# PIN_bias_voltage.net
KiCad netlist of a schematic drawn in Altium Designer
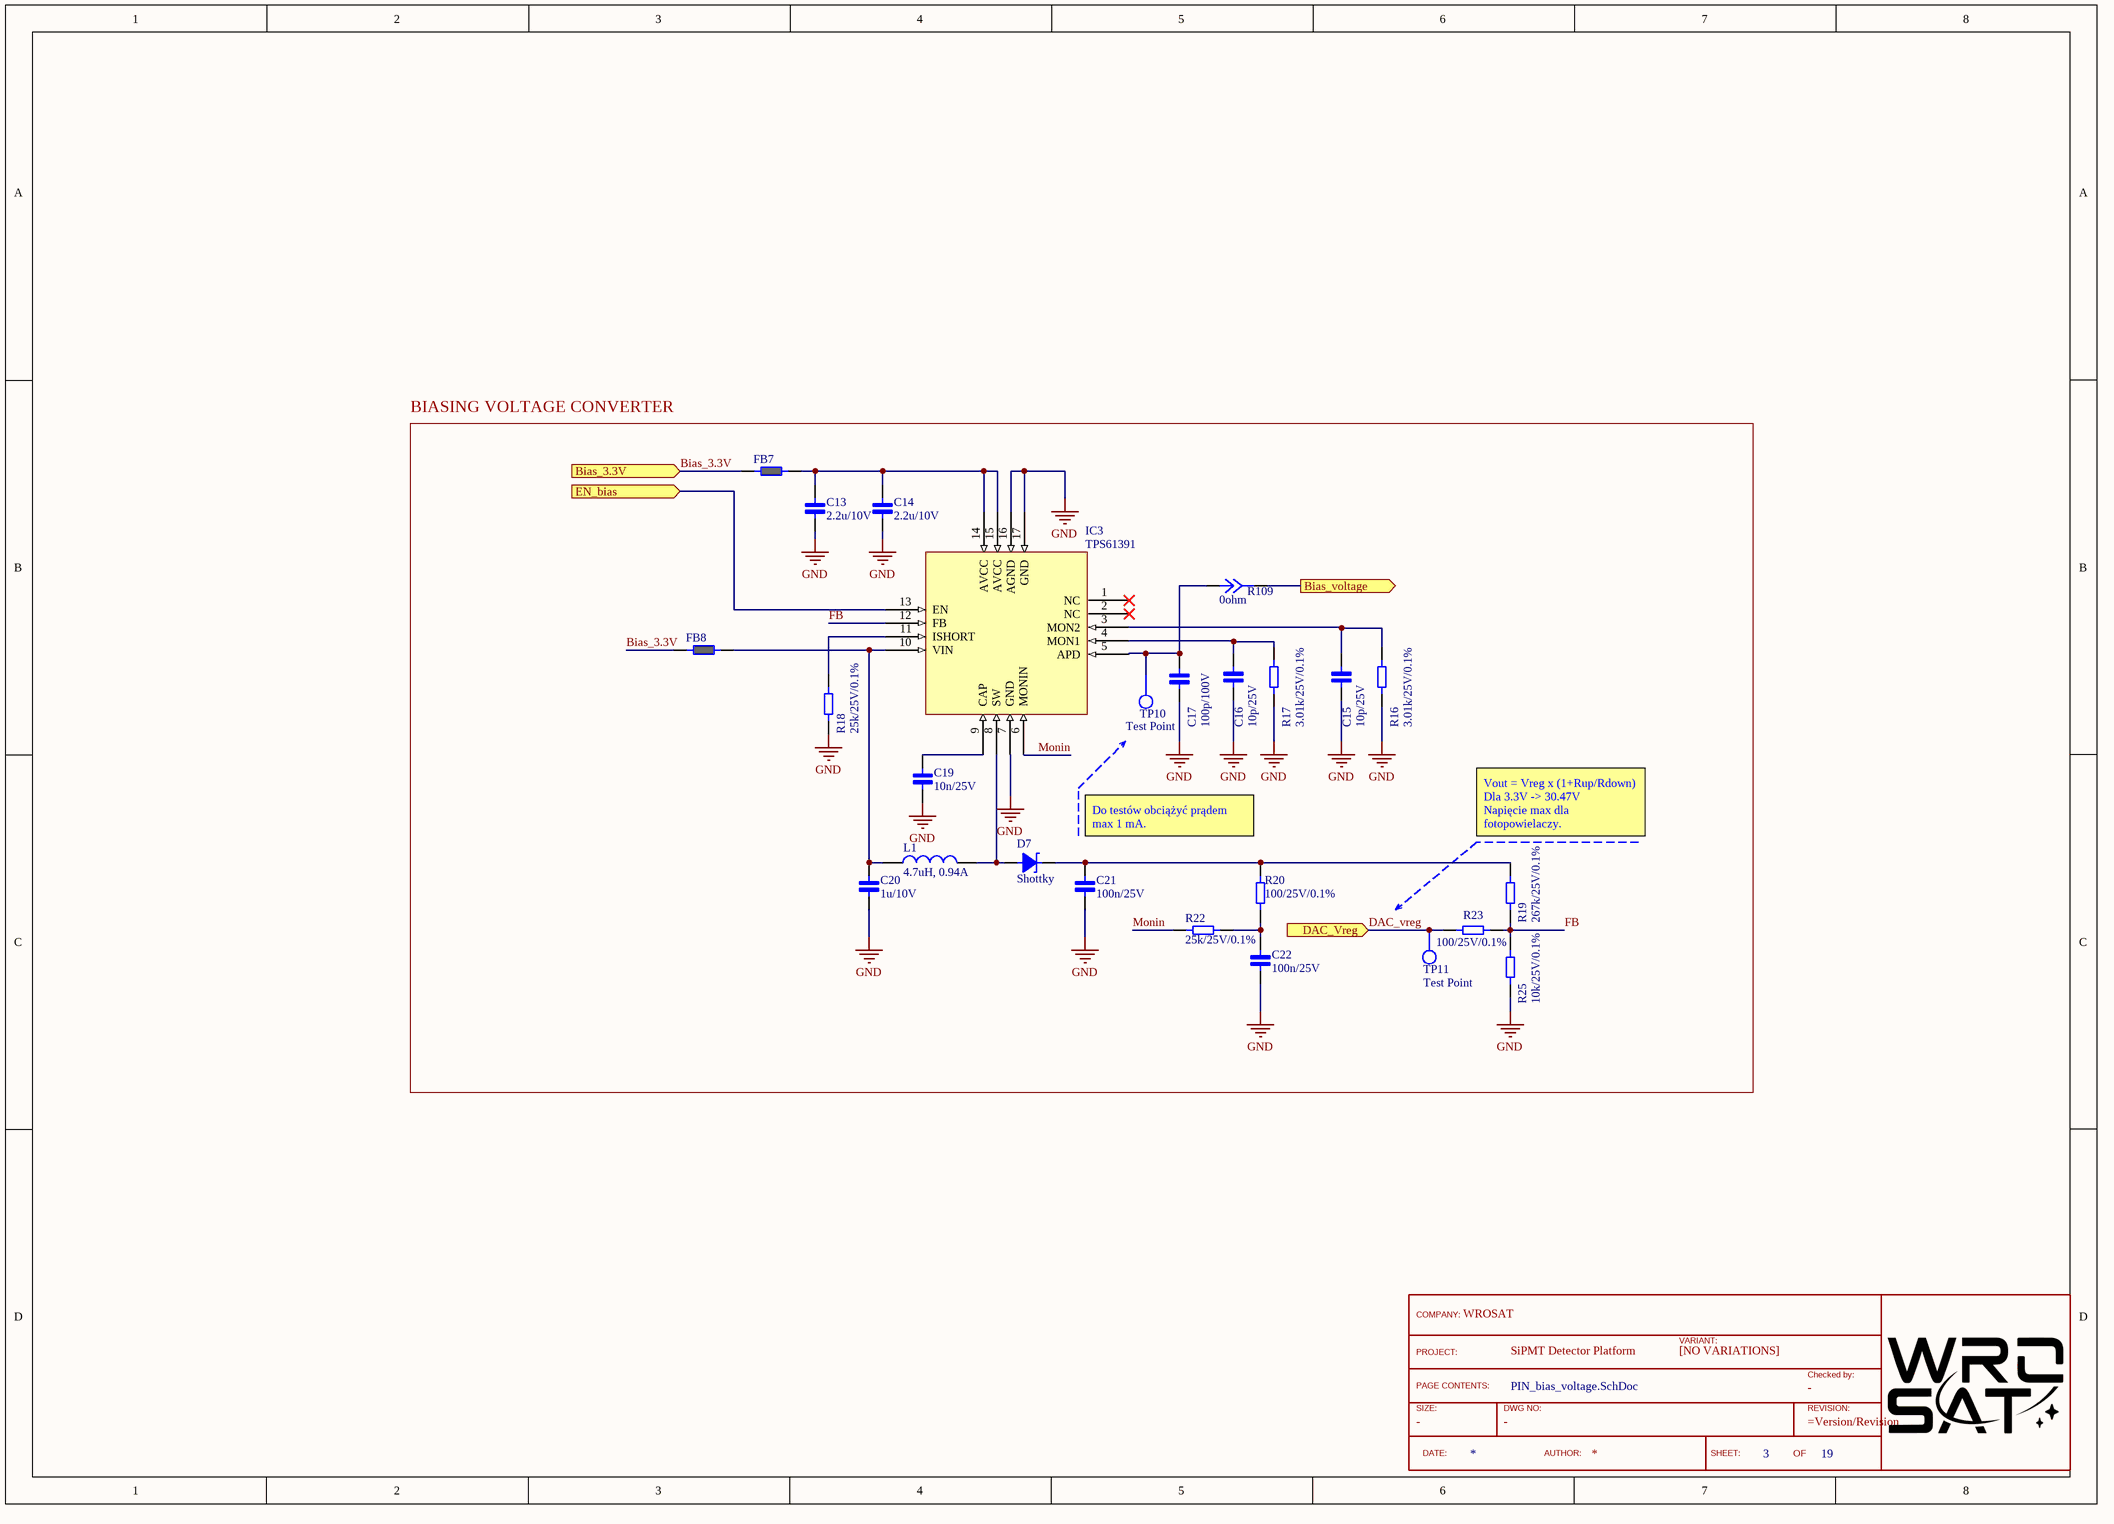
[diagram p0: PIN_bias_voltage.SchDoc]

(export (version "E")
  (design (tool "Eeschema 10.0.6"))
  (components
    (comp (ref "C13")
      (value "2.2u/10V")
      (footprint "Cap_0402")
      (description "Ceramic Capacitor 2.2uF / 0402 / 10V / ±5%, Wurth Elektronik MLCC")
      (libsource (lib "Cubesat_lib") (part "Cap_0402_2.2u"))
    )
    (comp (ref "C14")
      (value "2.2u/10V")
      (footprint "Cap_0402")
      (description "Ceramic Capacitor 2.2uF / 0402 / 10V / ±5%, Wurth Elektronik MLCC")
      (libsource (lib "Cubesat_lib") (part "Cap_0402_2.2u"))
    )
    (comp (ref "C15")
      (value "10p/25V")
      (footprint "Cap_0402")
      (description "0402 / 25V / ±5%, Wurth Elektronik MLCC")
      (libsource (lib "Cubesat_lib") (part "Cap_0402_10p"))
    )
    (comp (ref "C16")
      (value "10p/25V")
      (footprint "Cap_0402")
      (description "0402 / 25V / ±5%, Wurth Elektronik MLCC")
      (libsource (lib "Cubesat_lib") (part "Cap_0402_10p"))
    )
    (comp (ref "C17")
      (value "100p/100V")
      (footprint "Cap_0402")
      (description "0402 / 100V / ±5%, Wurth Elektronik MLCC")
      (libsource (lib "Cubesat_lib") (part "Cap_0402_100p_hv"))
    )
    (comp (ref "C19")
      (value "10n/25V")
      (footprint "Cap_0402")
      (description "Ceramic Capacitor 10n / 0402 / 25V / ±5%, Wurth Elektronik MLCC")
      (libsource (lib "Cubesat_lib") (part "Cap_0402_10n"))
    )
    (comp (ref "C20")
      (value "1u/10V")
      (footprint "Cap_0402")
      (description "Ceramic Capacitor 1uF / 0402 / 10V / ±5%, Wurth Elektronik MLCC")
      (libsource (lib "Cubesat_lib") (part "Cap_0402_1u"))
    )
    (comp (ref "C21")
      (value "100n/25V")
      (footprint "Cap_0402")
      (description "Ceramic Capacitor 100n / 0402 / 25V / ±5%, Wurth Elektronik MLCC")
      (libsource (lib "Cubesat_lib") (part "Cap_0402_100n"))
    )
    (comp (ref "C22")
      (value "100n/25V")
      (footprint "Cap_0402")
      (description "Ceramic Capacitor 100n / 0402 / 25V / ±5%, Wurth Elektronik MLCC")
      (libsource (lib "Cubesat_lib") (part "Cap_0402_100n"))
    )
    (comp (ref "D7")
      (value "Shottky")
      (footprint "SOD323")
      (description "Schottky diode, 90V, 100mA, 1.2V, 4ns")
      (libsource (lib "Cubesat_lib") (part "1SS355VMFHTE-17"))
    )
    (comp (ref "FB7")
      (value "Ferrite_bead_0402")
      (footprint "FERRITE_0402")
      (description "Ferrite bead, wurth 74269241102")
      (libsource (lib "Cubesat_lib") (part "Ferrite_bead_0402"))
    )
    (comp (ref "FB8")
      (value "Ferrite_bead_0402")
      (footprint "FERRITE_0402")
      (description "Ferrite bead, wurth 74269241102")
      (libsource (lib "Cubesat_lib") (part "Ferrite_bead_0402"))
    )
    (comp (ref "IC3")
      (value "TPS61391")
      (footprint "WQFN16")
      (description "TPS61391 85-VOUT Boost Converter with Current Mirror Integrated")
      (libsource (lib "Cubesat_lib") (part "TPS61391"))
    )
    (comp (ref "L1")
      (value "4.7uH, 0.94A")
      (footprint "WE-MAPI_2510")
      (description "WE-MAPI SMT Power Inductor, size 2510, 4.7uH, 0.94A")
      (fields
        (field (name "MANUFACTURER") "Wurth Elektronik")
        (field (name "MANUFACTURER PART NUMBER") "74438323047")
      )
      (libsource (lib "WE-MAPI_tiny_inductors") (part "74438323047"))
    )
    (comp (ref "R16")
      (value "3.01k/25V/0.1%")
      (footprint "RES_0402")
      (description "Vishay, thin film resistor 3.01k/25V/0.1%")
      (libsource (lib "Cubesat_lib") (part "Res_0402_3.01k"))
    )
    (comp (ref "R17")
      (value "3.01k/25V/0.1%")
      (footprint "RES_0402")
      (description "Vishay, thin film resistor 3.01k/25V/0.1%")
      (libsource (lib "Cubesat_lib") (part "Res_0402_3.01k"))
    )
    (comp (ref "R18")
      (value "25k/25V/0.1%")
      (footprint "RES_0402")
      (description "Vishay, thin film resistor 25k/25V/0.1%")
      (libsource (lib "Cubesat_lib") (part "Res_0402_25k"))
    )
    (comp (ref "R19")
      (value "267k/25V/0.1%")
      (footprint "RES_0402")
      (description "Vishay, thin film resistor 267k/25V/0.1%")
      (libsource (lib "Cubesat_lib") (part "Res_0402_267k"))
    )
    (comp (ref "R20")
      (value "100/25V/0.1%")
      (footprint "RES_0402")
      (description "Vishay, thin film resistor 100/25V/0.1%")
      (libsource (lib "") (part "Res_0402_100_1"))
    )
    (comp (ref "R22")
      (value "25k/25V/0.1%")
      (footprint "RES_0402")
      (description "Vishay, thin film resistor 25k/25V/0.1%")
      (libsource (lib "") (part "Res_0402_25k_1"))
    )
    (comp (ref "R23")
      (value "100/25V/0.1%")
      (footprint "RES_0402")
      (description "Vishay, thin film resistor 100/25V/0.1%")
      (libsource (lib "Cubesat_lib") (part "Res_0402_100"))
    )
    (comp (ref "R25")
      (value "10k/25V/0.1%")
      (footprint "RES_0402")
      (description "Vishay, thin film resistor 10k/25V/0.1%")
      (libsource (lib "Cubesat_lib") (part "Res_0402_10k"))
    )
    (comp (ref "R109") (value "0ohm") (footprint "Jumper 2") (libsource (lib "Cubesat_lib") (part "Jumper")))
    (comp (ref "TP10")
      (value "Test Point")
      (footprint "Test Point SMT")
      (libsource (lib "Cubesat_lib") (part "Test Point"))
    )
    (comp (ref "TP11")
      (value "Test Point")
      (footprint "Test Point SMT")
      (libsource (lib "Cubesat_lib") (part "Test Point"))
    )
  )
  (nets
    (net (code "1") (name "/Bias_3.3V") (class "Default")
      (node (ref "FB7") (pin "1") (pinfunction "1_1") (pintype "passive"))
      (node (ref "FB8") (pin "1") (pinfunction "1_1") (pintype "passive"))
    )
    (net (code "2") (name "/Bias_voltage") (class "Default")
      (node (ref "R109") (pin "2") (pinfunction "2_2") (pintype "passive"))
    )
    (net (code "3") (name "/DAC_vreg") (class "Default")
      (node (ref "R23") (pin "1") (pinfunction "1_1") (pintype "passive"))
      (node (ref "TP11") (pin "1") (pinfunction "1_1") (pintype "passive"))
    )
    (net (code "4") (name "/EN_bias") (class "Default")
      (node (ref "IC3") (pin "13") (pinfunction "EN_13") (pintype "input"))
    )
    (net (code "5") (name "/FB") (class "Default")
      (node (ref "IC3") (pin "12") (pinfunction "FB_12") (pintype "input"))
      (node (ref "R19") (pin "1") (pinfunction "1_1") (pintype "passive"))
      (node (ref "R23") (pin "2") (pinfunction "2_2") (pintype "passive"))
      (node (ref "R25") (pin "2") (pinfunction "2_2") (pintype "passive"))
    )
    (net (code "6") (name "/Monin") (class "Default")
      (node (ref "IC3") (pin "6") (pinfunction "MONIN_6") (pintype "input"))
      (node (ref "R22") (pin "1") (pinfunction "1_1") (pintype "passive"))
    )
    (net (code "7") (name "GND") (class "Default")
      (node (ref "C13") (pin "1") (pinfunction "1_1") (pintype "passive"))
      (node (ref "C14") (pin "1") (pinfunction "1_1") (pintype "passive"))
      (node (ref "C15") (pin "1") (pinfunction "1_1") (pintype "passive"))
      (node (ref "C16") (pin "1") (pinfunction "1_1") (pintype "passive"))
      (node (ref "C17") (pin "1") (pinfunction "1_1") (pintype "passive"))
      (node (ref "C19") (pin "1") (pinfunction "1_1") (pintype "passive"))
      (node (ref "C20") (pin "1") (pinfunction "1_1") (pintype "passive"))
      (node (ref "C21") (pin "1") (pinfunction "1_1") (pintype "passive"))
      (node (ref "C22") (pin "1") (pinfunction "1_1") (pintype "passive"))
      (node (ref "IC3") (pin "16") (pinfunction "AGND_16") (pintype "input"))
      (node (ref "IC3") (pin "17") (pinfunction "GND_17") (pintype "input"))
      (node (ref "IC3") (pin "7") (pinfunction "GND_7") (pintype "input"))
      (node (ref "R16") (pin "1") (pinfunction "1_1") (pintype "passive"))
      (node (ref "R17") (pin "1") (pinfunction "1_1") (pintype "passive"))
      (node (ref "R18") (pin "1") (pinfunction "1_1") (pintype "passive"))
      (node (ref "R25") (pin "1") (pinfunction "1_1") (pintype "passive"))
    )
    (net (code "8") (name "Net-(C13-Pad2)") (class "Default")
      (node (ref "C13") (pin "2") (pinfunction "2_2") (pintype "passive"))
      (node (ref "C14") (pin "2") (pinfunction "2_2") (pintype "passive"))
      (node (ref "FB7") (pin "2") (pinfunction "2_2") (pintype "passive"))
      (node (ref "IC3") (pin "14") (pinfunction "AVCC_14") (pintype "input"))
      (node (ref "IC3") (pin "15") (pinfunction "AVCC_15") (pintype "input"))
    )
    (net (code "9") (name "Net-(C21-Pad2)") (class "Default")
      (node (ref "C21") (pin "2") (pinfunction "2_2") (pintype "passive"))
      (node (ref "D7") (pin "2") (pinfunction "2_2") (pintype "passive"))
      (node (ref "R19") (pin "2") (pinfunction "2_2") (pintype "passive"))
      (node (ref "R20") (pin "2") (pinfunction "2_2") (pintype "passive"))
    )
    (net (code "10") (name "Net-(C22-Pad2)") (class "Default")
      (node (ref "C22") (pin "2") (pinfunction "2_2") (pintype "passive"))
      (node (ref "R20") (pin "1") (pinfunction "1_1") (pintype "passive"))
      (node (ref "R22") (pin "2") (pinfunction "2_2") (pintype "passive"))
    )
    (net (code "11") (name "Net-(IC3-APD)") (class "Default")
      (node (ref "C17") (pin "2") (pinfunction "2_2") (pintype "passive"))
      (node (ref "IC3") (pin "5") (pinfunction "APD_5") (pintype "input"))
      (node (ref "R109") (pin "1") (pinfunction "1_1") (pintype "passive"))
      (node (ref "TP10") (pin "1") (pinfunction "1_1") (pintype "passive"))
    )
    (net (code "12") (name "Net-(IC3-CAP)") (class "Default")
      (node (ref "C19") (pin "2") (pinfunction "2_2") (pintype "passive"))
      (node (ref "IC3") (pin "9") (pinfunction "CAP_9") (pintype "input"))
    )
    (net (code "13") (name "Net-(IC3-ISHORT)") (class "Default")
      (node (ref "IC3") (pin "11") (pinfunction "ISHORT_11") (pintype "input"))
      (node (ref "R18") (pin "2") (pinfunction "2_2") (pintype "passive"))
    )
    (net (code "14") (name "Net-(IC3-MON1)") (class "Default")
      (node (ref "C16") (pin "2") (pinfunction "2_2") (pintype "passive"))
      (node (ref "IC3") (pin "4") (pinfunction "MON1_4") (pintype "input"))
      (node (ref "R17") (pin "2") (pinfunction "2_2") (pintype "passive"))
    )
    (net (code "15") (name "Net-(IC3-MON2)") (class "Default")
      (node (ref "C15") (pin "2") (pinfunction "2_2") (pintype "passive"))
      (node (ref "IC3") (pin "3") (pinfunction "MON2_3") (pintype "input"))
      (node (ref "R16") (pin "2") (pinfunction "2_2") (pintype "passive"))
    )
    (net (code "16") (name "Net-(IC3-SW)") (class "Default")
      (node (ref "D7") (pin "1") (pinfunction "1_1") (pintype "passive"))
      (node (ref "IC3") (pin "8") (pinfunction "SW_8") (pintype "input"))
      (node (ref "L1") (pin "2") (pinfunction "2_2") (pintype "passive"))
    )
    (net (code "17") (name "Net-(IC3-VIN)") (class "Default")
      (node (ref "C20") (pin "2") (pinfunction "2_2") (pintype "passive"))
      (node (ref "FB8") (pin "2") (pinfunction "2_2") (pintype "passive"))
      (node (ref "IC3") (pin "10") (pinfunction "VIN_10") (pintype "input"))
      (node (ref "L1") (pin "1") (pinfunction "1_1") (pintype "passive"))
    )
    (net (code "18") (name "unconnected-(IC3-NC-Pad1)") (class "Default")
      (node (ref "IC3") (pin "1") (pinfunction "NC_1") (pintype "passive+no_connect"))
    )
    (net (code "19") (name "unconnected-(IC3-NC-Pad2)") (class "Default")
      (node (ref "IC3") (pin "2") (pinfunction "NC_2") (pintype "passive+no_connect"))
    )
  )
)
